# 02_MCU_connector.net
KiCad netlist of a schematic drawn in Altium Designer
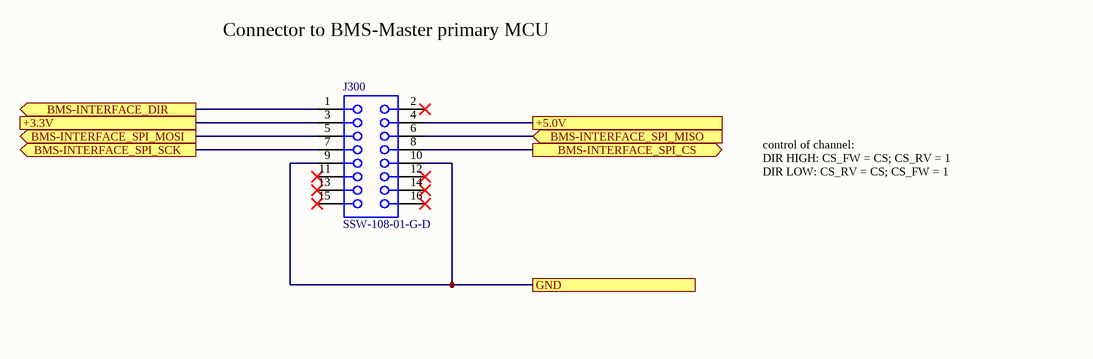
[diagram p0: 02_MCU_connector.SchDoc]

(export (version "E")
  (design (tool "Eeschema 10.0.6"))
  (components
    (comp (ref "J300")
      (value "SSW-108-01-G-D")
      (footprint "SMTC-SSW-108-01-X-D")
      (description "SQ Post Socket, Through-hole, Vertical, -55 to 125 degC, 2.54mm Pitch, 16-Pin, Female, RoHS")
      (fields (field (name "MANUFACTURER") "Samtec"))
      (libsource (lib "Altium Content Vault") (part "SMTC-SSW-108-X-X-D-X"))
    )
  )
  (nets
    (net (code "1") (name "/+3.3V") (class "Default")
      (node (ref "J300") (pin "3") (pinfunction "3_3") (pintype "passive"))
    )
    (net (code "2") (name "/+5.0V") (class "Default")
      (node (ref "J300") (pin "4") (pinfunction "4_4") (pintype "passive"))
    )
    (net (code "3") (name "/BMS-INTERFACE_DIR") (class "Default")
      (node (ref "J300") (pin "1") (pinfunction "1_1") (pintype "passive"))
    )
    (net (code "4") (name "/BMS-INTERFACE_SPI_CS") (class "Default")
      (node (ref "J300") (pin "8") (pinfunction "8_8") (pintype "passive"))
    )
    (net (code "5") (name "/BMS-INTERFACE_SPI_MISO") (class "Default")
      (node (ref "J300") (pin "6") (pinfunction "6_6") (pintype "passive"))
    )
    (net (code "6") (name "/BMS-INTERFACE_SPI_MOSI") (class "Default")
      (node (ref "J300") (pin "5") (pinfunction "5_5") (pintype "passive"))
    )
    (net (code "7") (name "/BMS-INTERFACE_SPI_SCK") (class "Default")
      (node (ref "J300") (pin "7") (pinfunction "7_7") (pintype "passive"))
    )
    (net (code "8") (name "/GND") (class "Default")
      (node (ref "J300") (pin "10") (pinfunction "10_10") (pintype "passive"))
      (node (ref "J300") (pin "9") (pinfunction "9_9") (pintype "passive"))
    )
    (net (code "9") (name "unconnected-(J300-Pad2)") (class "Default")
      (node (ref "J300") (pin "2") (pinfunction "2_2") (pintype "passive+no_connect"))
    )
    (net (code "10") (name "unconnected-(J300-Pad11)") (class "Default")
      (node (ref "J300") (pin "11") (pinfunction "11_11") (pintype "passive+no_connect"))
    )
    (net (code "11") (name "unconnected-(J300-Pad12)") (class "Default")
      (node (ref "J300") (pin "12") (pinfunction "12_12") (pintype "passive+no_connect"))
    )
    (net (code "12") (name "unconnected-(J300-Pad13)") (class "Default")
      (node (ref "J300") (pin "13") (pinfunction "13_13") (pintype "passive+no_connect"))
    )
    (net (code "13") (name "unconnected-(J300-Pad14)") (class "Default")
      (node (ref "J300") (pin "14") (pinfunction "14_14") (pintype "passive+no_connect"))
    )
    (net (code "14") (name "unconnected-(J300-Pad15)") (class "Default")
      (node (ref "J300") (pin "15") (pinfunction "15_15") (pintype "passive+no_connect"))
    )
    (net (code "15") (name "unconnected-(J300-Pad16)") (class "Default")
      (node (ref "J300") (pin "16") (pinfunction "16_16") (pintype "passive+no_connect"))
    )
  )
)
